# project_zasetskiy_DC-DC.net
KiCad netlist of a schematic drawn in Altium Designer
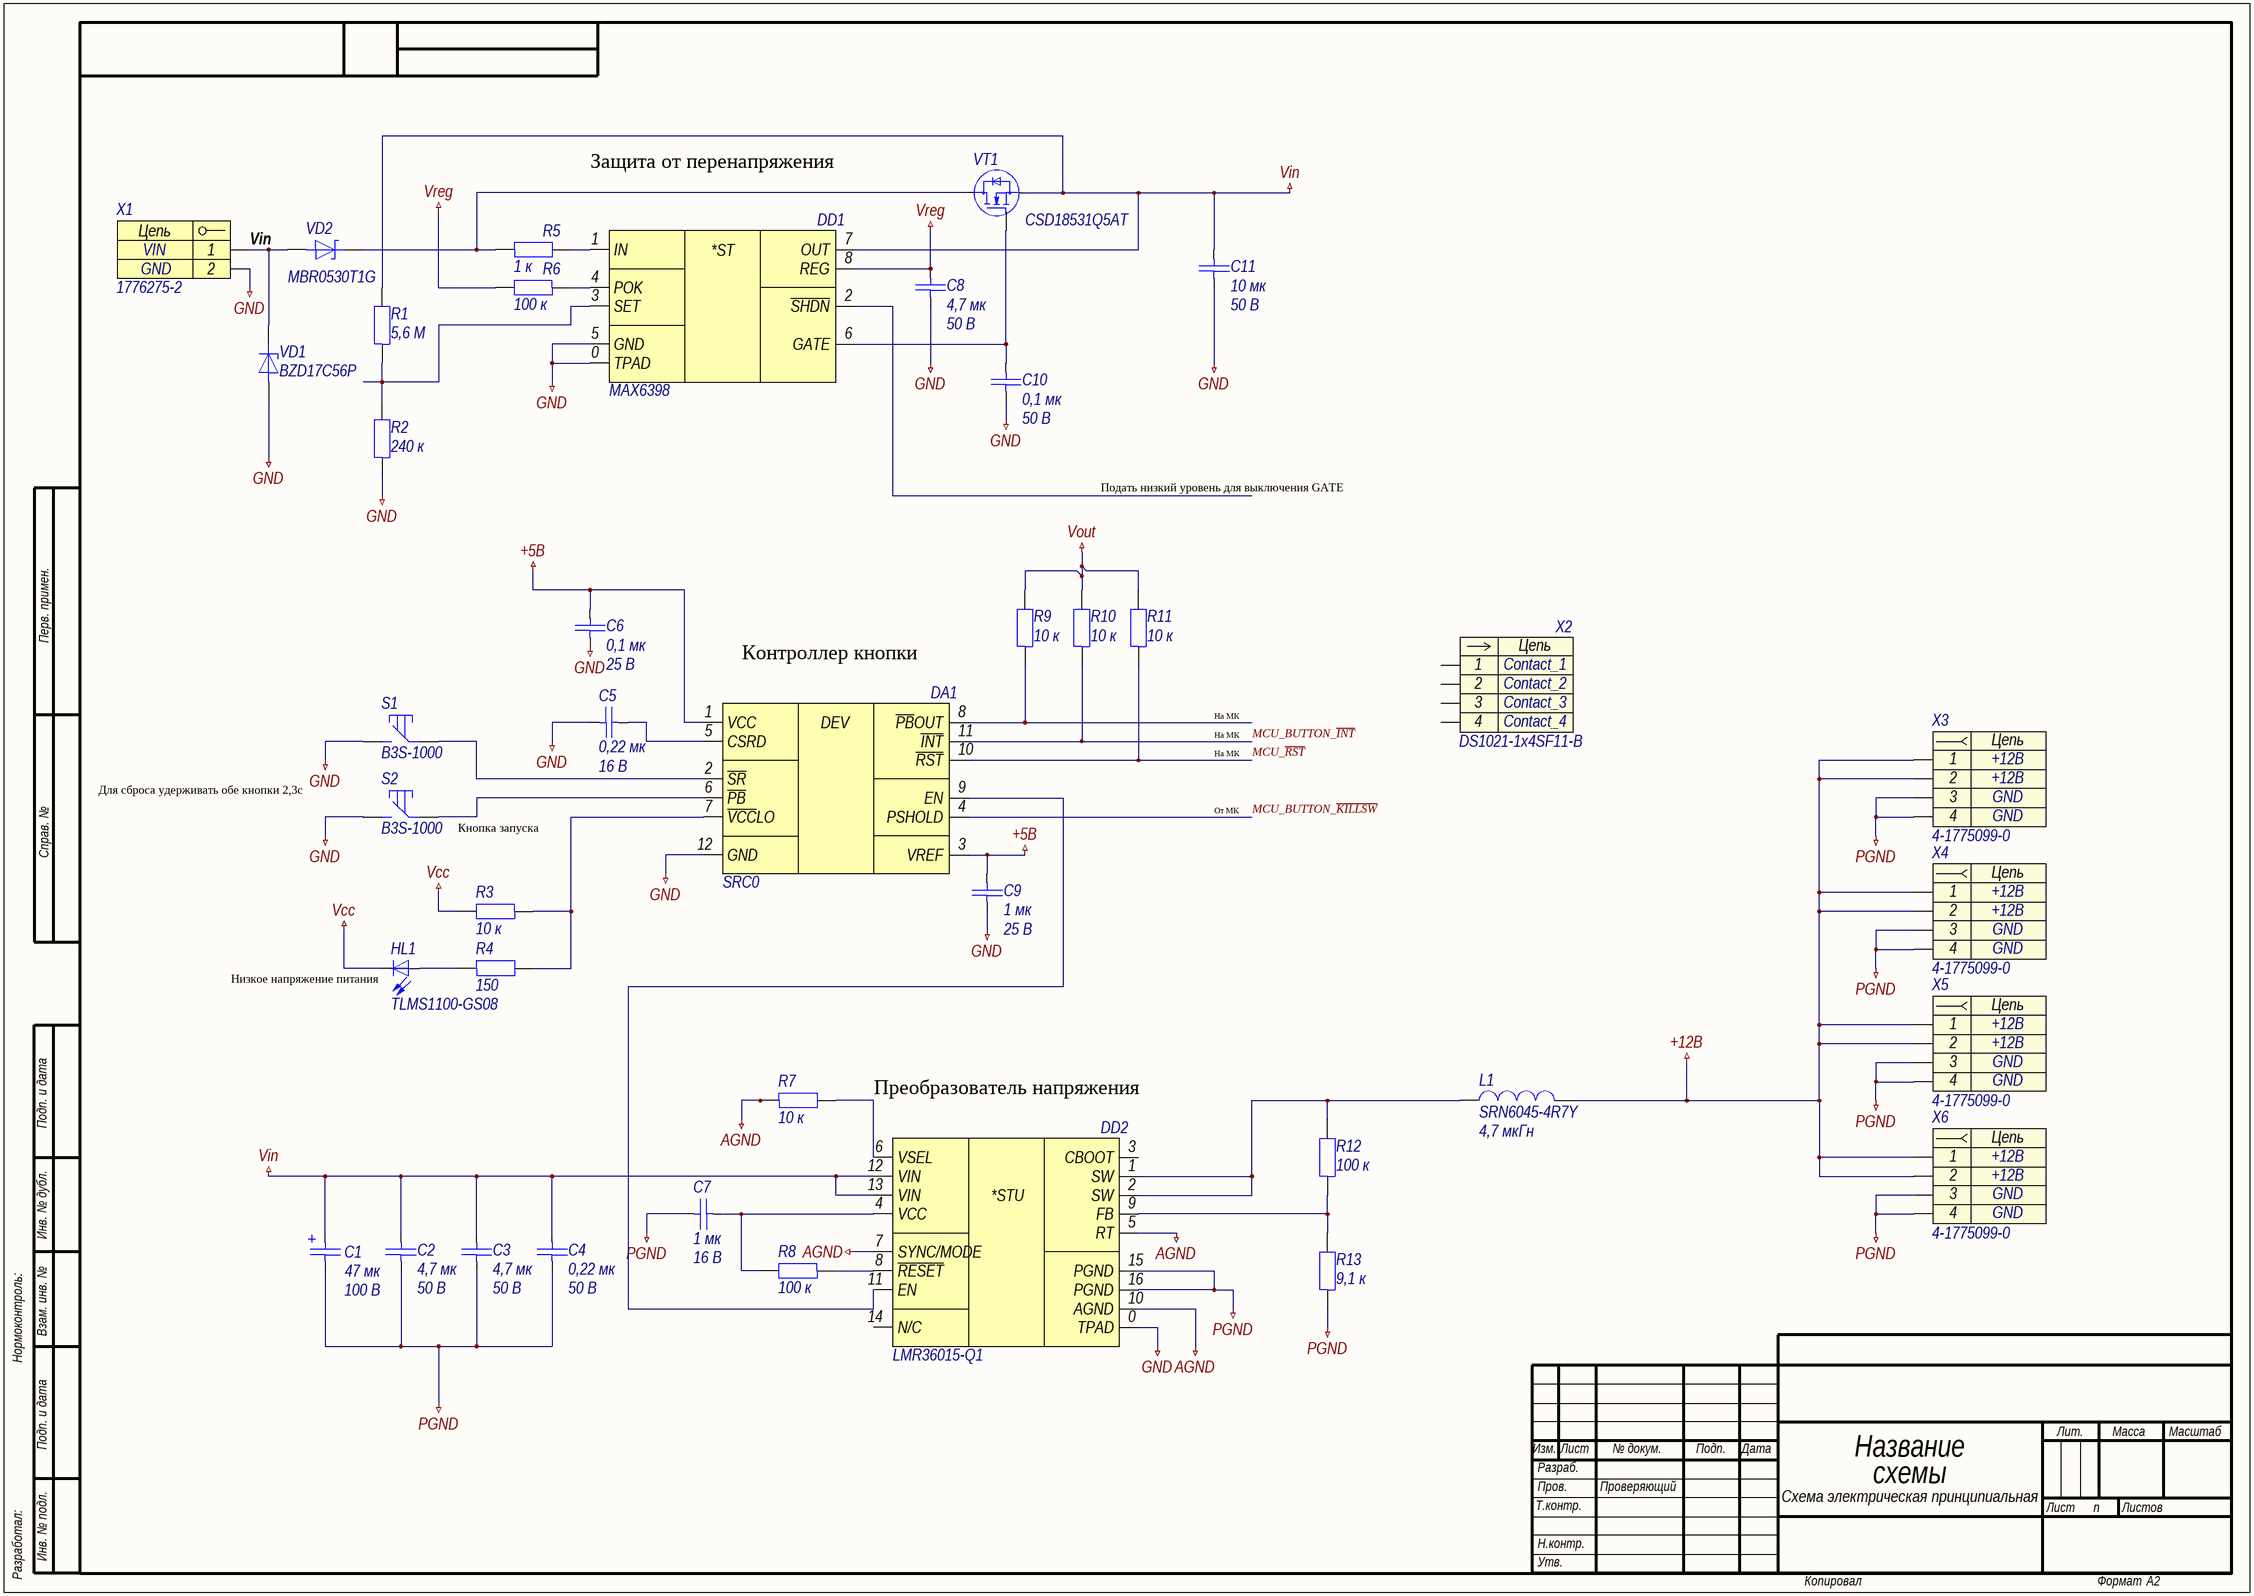
[diagram p0: project_zasetskiy_DC-DC.SchDoc]

(export (version "E")
  (design (tool "Eeschema 10.0.6"))
  (components
    (comp (ref "C1")
      (value "47 мк")
      (footprint "CAPAE-1000X1000X1200")
      (description "=Описание")
      (fields (field (name "НАПРЯЖЕНИЕ") "100 В"))
      (libsource (lib "Database_Students") (part "CAPACITOR-POLAR"))
    )
    (comp (ref "C2")
      (value "4,7 мк")
      (footprint "C1206")
      (description "=Описание")
      (fields (field (name "НАПРЯЖЕНИЕ") "50 В"))
      (libsource (lib "Database_Students") (part "CAPACITOR-NONPOLAR"))
    )
    (comp (ref "C3")
      (value "4,7 мк")
      (footprint "C1206")
      (description "=Описание")
      (fields (field (name "НАПРЯЖЕНИЕ") "50 В"))
      (libsource (lib "Database_Students") (part "CAPACITOR-NONPOLAR"))
    )
    (comp (ref "C4")
      (value "0,22 мк")
      (footprint "C0603")
      (description "=Описание")
      (fields (field (name "НАПРЯЖЕНИЕ") "50 В"))
      (libsource (lib "Database_Students") (part "CAPACITOR-NONPOLAR"))
    )
    (comp (ref "C5")
      (value "0,22 мк")
      (footprint "C0603")
      (description "=Описание")
      (fields (field (name "НАПРЯЖЕНИЕ") "16 В"))
      (libsource (lib "Database_Students") (part "CAPACITOR-NONPOLAR"))
    )
    (comp (ref "C6")
      (value "0,1 мк")
      (footprint "C0402")
      (description "=Описание")
      (fields (field (name "НАПРЯЖЕНИЕ") "25 В"))
      (libsource (lib "Database_Students") (part "CAPACITOR-NONPOLAR"))
    )
    (comp (ref "C7")
      (value "1 мк")
      (footprint "C0603")
      (description "=Описание")
      (fields (field (name "НАПРЯЖЕНИЕ") "16 В"))
      (libsource (lib "Database_Students") (part "CAPACITOR-NONPOLAR"))
    )
    (comp (ref "C8")
      (value "4,7 мк")
      (footprint "C1206")
      (description "=Описание")
      (fields (field (name "НАПРЯЖЕНИЕ") "50 В"))
      (libsource (lib "Database_Students") (part "CAPACITOR-NONPOLAR"))
    )
    (comp (ref "C9")
      (value "1 мк")
      (footprint "C0603")
      (description "=Описание")
      (fields (field (name "НАПРЯЖЕНИЕ") "25 В"))
      (libsource (lib "Database_Students") (part "CAPACITOR-NONPOLAR"))
    )
    (comp (ref "C10")
      (value "0,1 мк")
      (footprint "C0603")
      (description "=Описание")
      (fields (field (name "НАПРЯЖЕНИЕ") "50 В"))
      (libsource (lib "Database_Students") (part "CAPACITOR-NONPOLAR"))
    )
    (comp (ref "C11")
      (value "10 мк")
      (footprint "C1210")
      (description "=Описание")
      (fields (field (name "НАПРЯЖЕНИЕ") "50 В"))
      (libsource (lib "Database_Students") (part "CAPACITOR-NONPOLAR"))
    )
    (comp (ref "DA1")
      (value "SRC0")
      (description "=Описание")
      (libsource (lib "MyDatabase") (part "DA-SRC0"))
    )
    (comp (ref "DD1")
      (value "MAX6398")
      (description "=Описание")
      (libsource (lib "MyDatabase") (part "DD-MAX6398"))
    )
    (comp (ref "DD2")
      (value "LMR36015-Q1")
      (description "=Описание")
      (libsource (lib "MyDatabase") (part "DD-LM63635-Q1"))
    )
    (comp (ref "HL1")
      (value "TLMS1100-GS08")
      (footprint "LED")
      (description "=Описание")
      (libsource (lib "MyDatabase") (part "led"))
    )
    (comp (ref "L1")
      (value "SRN6045-4R7Y")
      (footprint "SRN-2-600X600X450")
      (description "=Описание")
      (fields (field (name "ИНДУКТИВНОСТЬ") "4,7 мкГн"))
      (libsource (lib "Database_Students") (part "INDUCTOR-COMMON"))
    )
    (comp (ref "R1")
      (value "5,6 M")
      (footprint "R0603")
      (description "=Описание")
      (libsource (lib "Database_Students") (part "RESISTOR-COMMON"))
    )
    (comp (ref "R2")
      (value "240 к")
      (footprint "R0603")
      (description "=Описание")
      (libsource (lib "Database_Students") (part "RESISTOR-COMMON"))
    )
    (comp (ref "R3")
      (value "10 к")
      (footprint "R0603")
      (description "=Описание")
      (libsource (lib "Database_Students") (part "RESISTOR-COMMON"))
    )
    (comp (ref "R4")
      (value "150")
      (footprint "R0603")
      (description "=Описание")
      (libsource (lib "Database_Students") (part "RESISTOR-COMMON"))
    )
    (comp (ref "R5")
      (value "1 к")
      (footprint "R0603")
      (description "=Описание")
      (libsource (lib "Database_Students") (part "RESISTOR-COMMON"))
    )
    (comp (ref "R6")
      (value "100 к")
      (footprint "R0603")
      (description "=Описание")
      (libsource (lib "Database_Students") (part "RESISTOR-COMMON"))
    )
    (comp (ref "R7")
      (value "10 к")
      (footprint "R0603")
      (description "=Описание")
      (libsource (lib "Database_Students") (part "RESISTOR-COMMON"))
    )
    (comp (ref "R8")
      (value "100 к")
      (footprint "R0603")
      (description "=Описание")
      (libsource (lib "Database_Students") (part "RESISTOR-COMMON"))
    )
    (comp (ref "R9")
      (value "10 к")
      (footprint "R0603")
      (description "=Описание")
      (libsource (lib "Database_Students") (part "RESISTOR-COMMON"))
    )
    (comp (ref "R10")
      (value "10 к")
      (footprint "R0603")
      (description "=Описание")
      (libsource (lib "Database_Students") (part "RESISTOR-COMMON"))
    )
    (comp (ref "R11")
      (value "10 к")
      (footprint "R0603")
      (description "=Описание")
      (libsource (lib "Database_Students") (part "RESISTOR-COMMON"))
    )
    (comp (ref "R12")
      (value "100 к")
      (footprint "R0603")
      (description "=Описание")
      (libsource (lib "Database_Students") (part "RESISTOR-COMMON"))
    )
    (comp (ref "R13")
      (value "9,1 к")
      (footprint "R0603")
      (description "=Описание")
      (libsource (lib "Database_Students") (part "RESISTOR-COMMON"))
    )
    (comp (ref "S1")
      (value "B3S-1000")
      (footprint "BUTTON")
      (description "=Описание")
      (libsource (lib "MyDatabase") (part "S-button"))
    )
    (comp (ref "S2")
      (value "B3S-1000")
      (footprint "BUTTON")
      (description "=Описание")
      (libsource (lib "MyDatabase") (part "S-button"))
    )
    (comp (ref "VD1")
      (value "BZD17C56P")
      (footprint "DO-219AB-280X180X108")
      (description "=Описание")
      (libsource (lib "Database_Students") (part "DIODE-ZENER"))
    )
    (comp (ref "VD2")
      (value "MBR0530T1G")
      (footprint "SOD-123-368X160X135")
      (description "=Описание")
      (libsource (lib "Database_Students") (part "DIODE-SCHOTTKY"))
    )
    (comp (ref "VT1")
      (value "CSD18531Q5AT")
      (footprint "VSONP-8-P127-600X500X110")
      (description "=Описание")
      (libsource (lib "Database_Students") (part "MOSFET-N-DIODE"))
    )
    (comp (ref "X1")
      (value "1776275-2")
      (footprint "1776275-2")
      (description "=Описание")
      (libsource (lib "Database_Students") (part "HEADER-2-TRM"))
    )
    (comp (ref "X2")
      (value "DS1021-1x4SF11-B")
      (footprint "DS1021-1X4SF11-B")
      (description "=Описание")
      (libsource (lib "Database_Students") (part "HEADER-4-PLG"))
    )
    (comp (ref "X3")
      (value "4-1775099-0")
      (footprint "4-1775099-0")
      (description "=Описание")
      (libsource (lib "Database_Students") (part "HEADER-4-SCT"))
    )
    (comp (ref "X4")
      (value "4-1775099-0")
      (footprint "4-1775099-0")
      (description "=Описание")
      (libsource (lib "Database_Students") (part "HEADER-4-SCT"))
    )
    (comp (ref "X5")
      (value "4-1775099-0")
      (footprint "4-1775099-0")
      (description "=Описание")
      (libsource (lib "Database_Students") (part "HEADER-4-SCT"))
    )
    (comp (ref "X6")
      (value "4-1775099-0")
      (footprint "4-1775099-0")
      (description "=Описание")
      (libsource (lib "Database_Students") (part "HEADER-4-SCT"))
    )
  )
  (nets
    (net (code "1") (name "+5В") (class "Default")
      (node (ref "C6") (pin "1") (pinfunction "1_1") (pintype "passive"))
      (node (ref "C9") (pin "1") (pinfunction "1_1") (pintype "passive"))
      (node (ref "DA1") (pin "1") (pinfunction "VCC_1") (pintype "passive"))
      (node (ref "DA1") (pin "3") (pinfunction "VREF_3") (pintype "passive"))
    )
    (net (code "2") (name "+12В") (class "Default")
      (node (ref "L1") (pin "2") (pinfunction "2_2") (pintype "passive"))
      (node (ref "X3") (pin "1") (pinfunction "1_1") (pintype "passive"))
      (node (ref "X3") (pin "2") (pinfunction "2_2") (pintype "passive"))
      (node (ref "X4") (pin "1") (pinfunction "1_1") (pintype "passive"))
      (node (ref "X4") (pin "2") (pinfunction "2_2") (pintype "passive"))
      (node (ref "X5") (pin "1") (pinfunction "1_1") (pintype "passive"))
      (node (ref "X5") (pin "2") (pinfunction "2_2") (pintype "passive"))
      (node (ref "X6") (pin "1") (pinfunction "1_1") (pintype "passive"))
      (node (ref "X6") (pin "2") (pinfunction "2_2") (pintype "passive"))
    )
    (net (code "3") (name "/MCU_BUTTON_~{INT}") (class "Default")
      (node (ref "DA1") (pin "11") (pinfunction "~{INT}_11") (pintype "passive"))
      (node (ref "R10") (pin "1") (pinfunction "1_1") (pintype "passive"))
    )
    (net (code "4") (name "/MCU_BUTTON_~{KILLSW}") (class "Default")
      (node (ref "DA1") (pin "4") (pinfunction "PSHOLD_4") (pintype "passive"))
    )
    (net (code "5") (name "/MCU_~{RST}") (class "Default")
      (node (ref "DA1") (pin "10") (pinfunction "~{RST}_10") (pintype "passive"))
      (node (ref "R11") (pin "1") (pinfunction "1_1") (pintype "passive"))
    )
    (net (code "6") (name "AGND") (class "Default")
      (node (ref "DD2") (pin "10") (pinfunction "AGND_10") (pintype "passive"))
      (node (ref "DD2") (pin "5") (pinfunction "RT_5") (pintype "passive"))
      (node (ref "DD2") (pin "7") (pinfunction "SYNC/MODE_7") (pintype "passive"))
      (node (ref "R7") (pin "1") (pinfunction "1_1") (pintype "passive"))
    )
    (net (code "7") (name "GND") (class "Default")
      (node (ref "C10") (pin "2") (pinfunction "2_2") (pintype "passive"))
      (node (ref "C11") (pin "2") (pinfunction "2_2") (pintype "passive"))
      (node (ref "C5") (pin "2") (pinfunction "2_2") (pintype "passive"))
      (node (ref "C6") (pin "2") (pinfunction "2_2") (pintype "passive"))
      (node (ref "C8") (pin "2") (pinfunction "2_2") (pintype "passive"))
      (node (ref "C9") (pin "2") (pinfunction "2_2") (pintype "passive"))
      (node (ref "DA1") (pin "12") (pinfunction "GND_12") (pintype "passive"))
      (node (ref "DD1") (pin "0") (pinfunction "TPAD_0") (pintype "passive"))
      (node (ref "DD1") (pin "5") (pinfunction "GND_5") (pintype "passive"))
      (node (ref "DD2") (pin "0") (pinfunction "TPAD_0") (pintype "passive"))
      (node (ref "R2") (pin "1") (pinfunction "1_1") (pintype "passive"))
      (node (ref "VD1") (pin "2") (pinfunction "2_2") (pintype "passive"))
      (node (ref "X1") (pin "2") (pinfunction "2_2") (pintype "passive"))
    )
    (net (code "8") (name "Net-(DA1-CSRD)") (class "Default")
      (node (ref "C5") (pin "1") (pinfunction "1_1") (pintype "passive"))
      (node (ref "DA1") (pin "5") (pinfunction "CSRD_5") (pintype "passive"))
    )
    (net (code "9") (name "Net-(DA1-EN)") (class "Default")
      (node (ref "DA1") (pin "9") (pinfunction "EN_9") (pintype "passive"))
      (node (ref "DD2") (pin "11") (pinfunction "EN_11") (pintype "passive"))
    )
    (net (code "10") (name "Net-(DA1-~{PB})") (class "Default")
      (node (ref "DA1") (pin "6") (pinfunction "~{PB}_6") (pintype "passive"))
      (node (ref "S2") (pin "2") (pinfunction "2_2") (pintype "passive"))
    )
    (net (code "11") (name "Net-(DA1-~{PB}OUT)") (class "Default")
      (node (ref "DA1") (pin "8") (pinfunction "~{PB}OUT_8") (pintype "passive"))
      (node (ref "R9") (pin "1") (pinfunction "1_1") (pintype "passive"))
    )
    (net (code "12") (name "Net-(DA1-~{SR})") (class "Default")
      (node (ref "DA1") (pin "2") (pinfunction "~{SR}_2") (pintype "passive"))
      (node (ref "S1") (pin "2") (pinfunction "2_2") (pintype "passive"))
    )
    (net (code "13") (name "Net-(DA1-~{VCC}LO)") (class "Default")
      (node (ref "DA1") (pin "7") (pinfunction "~{VCC}LO_7") (pintype "passive"))
      (node (ref "R3") (pin "1") (pinfunction "1_1") (pintype "passive"))
      (node (ref "R4") (pin "2") (pinfunction "2_2") (pintype "passive"))
    )
    (net (code "14") (name "Net-(DD1-GATE)") (class "Default")
      (node (ref "C10") (pin "1") (pinfunction "1_1") (pintype "passive"))
      (node (ref "DD1") (pin "6") (pinfunction "GATE_6") (pintype "passive"))
      (node (ref "VT1") (pin "G") (pinfunction "G_G") (pintype "passive"))
    )
    (net (code "15") (name "Net-(DD1-IN)") (class "Default")
      (node (ref "DD1") (pin "1") (pinfunction "IN_1") (pintype "passive"))
      (node (ref "R5") (pin "2") (pinfunction "2_2") (pintype "passive"))
    )
    (net (code "16") (name "Net-(DD1-POK)") (class "Default")
      (node (ref "DD1") (pin "4") (pinfunction "POK_4") (pintype "passive"))
      (node (ref "R6") (pin "1") (pinfunction "1_1") (pintype "passive"))
    )
    (net (code "17") (name "Net-(DD1-SET)") (class "Default")
      (node (ref "DD1") (pin "3") (pinfunction "SET_3") (pintype "passive"))
      (node (ref "R1") (pin "1") (pinfunction "1_1") (pintype "passive"))
      (node (ref "R2") (pin "2") (pinfunction "2_2") (pintype "passive"))
    )
    (net (code "18") (name "Net-(DD2-FB)") (class "Default")
      (node (ref "DD2") (pin "9") (pinfunction "FB_9") (pintype "passive"))
      (node (ref "R12") (pin "1") (pinfunction "1_1") (pintype "passive"))
      (node (ref "R13") (pin "2") (pinfunction "2_2") (pintype "passive"))
    )
    (net (code "19") (name "Net-(DD2-SW-Pad1)") (class "Default")
      (node (ref "DD2") (pin "1") (pinfunction "SW_1") (pintype "passive"))
      (node (ref "DD2") (pin "2") (pinfunction "SW_2") (pintype "passive"))
      (node (ref "L1") (pin "1") (pinfunction "1_1") (pintype "passive"))
      (node (ref "R12") (pin "2") (pinfunction "2_2") (pintype "passive"))
    )
    (net (code "20") (name "Net-(DD2-VCC)") (class "Default")
      (node (ref "C7") (pin "2") (pinfunction "2_2") (pintype "passive"))
      (node (ref "DD2") (pin "4") (pinfunction "VCC_4") (pintype "passive"))
      (node (ref "R8") (pin "2") (pinfunction "2_2") (pintype "passive"))
    )
    (net (code "21") (name "Net-(DD2-VSEL)") (class "Default")
      (node (ref "DD2") (pin "6") (pinfunction "VSEL_6") (pintype "passive"))
      (node (ref "R7") (pin "2") (pinfunction "2_2") (pintype "passive"))
    )
    (net (code "22") (name "Net-(DD2-~{RESET})") (class "Default")
      (node (ref "DD2") (pin "8") (pinfunction "~{RESET}_8") (pintype "passive"))
      (node (ref "R8") (pin "1") (pinfunction "1_1") (pintype "passive"))
    )
    (net (code "23") (name "Net-(HL1-A)") (class "Default")
      (node (ref "HL1") (pin "1") (pinfunction "A_1") (pintype "passive"))
      (node (ref "R4") (pin "1") (pinfunction "1_1") (pintype "passive"))
    )
    (net (code "24") (name "Net-(R5-Pad1)") (class "Default")
      (node (ref "R5") (pin "1") (pinfunction "1_1") (pintype "passive"))
      (node (ref "VD2") (pin "1") (pinfunction "1_1") (pintype "passive"))
      (node (ref "VT1") (pin "D") (pinfunction "D_D") (pintype "passive"))
    )
    (net (code "25") (name "Net-(VD1-Pad1)") (class "Default")
      (node (ref "VD1") (pin "1") (pinfunction "1_1") (pintype "passive"))
      (node (ref "VD2") (pin "2") (pinfunction "2_2") (pintype "passive"))
      (node (ref "X1") (pin "1") (pinfunction "1_1") (pintype "passive"))
    )
    (net (code "26") (name "PGND") (class "Default")
      (node (ref "C1") (pin "2") (pinfunction "2_2") (pintype "passive"))
      (node (ref "C2") (pin "2") (pinfunction "2_2") (pintype "passive"))
      (node (ref "C3") (pin "2") (pinfunction "2_2") (pintype "passive"))
      (node (ref "C4") (pin "2") (pinfunction "2_2") (pintype "passive"))
      (node (ref "C7") (pin "1") (pinfunction "1_1") (pintype "passive"))
      (node (ref "DD2") (pin "15") (pinfunction "PGND_15") (pintype "passive"))
      (node (ref "DD2") (pin "16") (pinfunction "PGND_16") (pintype "passive"))
      (node (ref "R13") (pin "1") (pinfunction "1_1") (pintype "passive"))
      (node (ref "X3") (pin "3") (pinfunction "3_3") (pintype "passive"))
      (node (ref "X3") (pin "4") (pinfunction "4_4") (pintype "passive"))
      (node (ref "X4") (pin "3") (pinfunction "3_3") (pintype "passive"))
      (node (ref "X4") (pin "4") (pinfunction "4_4") (pintype "passive"))
      (node (ref "X5") (pin "3") (pinfunction "3_3") (pintype "passive"))
      (node (ref "X5") (pin "4") (pinfunction "4_4") (pintype "passive"))
      (node (ref "X6") (pin "3") (pinfunction "3_3") (pintype "passive"))
      (node (ref "X6") (pin "4") (pinfunction "4_4") (pintype "passive"))
    )
    (net (code "27") (name "Vcc") (class "Default")
      (node (ref "HL1") (pin "2") (pinfunction "K_2") (pintype "passive"))
      (node (ref "R3") (pin "2") (pinfunction "2_2") (pintype "passive"))
    )
    (net (code "28") (name "Vin") (class "Default")
      (node (ref "C1") (pin "1") (pinfunction "1_1") (pintype "passive"))
      (node (ref "C11") (pin "1") (pinfunction "1_1") (pintype "passive"))
      (node (ref "C2") (pin "1") (pinfunction "1_1") (pintype "passive"))
      (node (ref "C3") (pin "1") (pinfunction "1_1") (pintype "passive"))
      (node (ref "C4") (pin "1") (pinfunction "1_1") (pintype "passive"))
      (node (ref "DD1") (pin "7") (pinfunction "OUT_7") (pintype "passive"))
      (node (ref "DD2") (pin "12") (pinfunction "VIN_12") (pintype "passive"))
      (node (ref "DD2") (pin "13") (pinfunction "VIN_13") (pintype "passive"))
      (node (ref "R1") (pin "2") (pinfunction "2_2") (pintype "passive"))
      (node (ref "VT1") (pin "S") (pinfunction "S_S") (pintype "passive"))
    )
    (net (code "29") (name "Vout") (class "Default")
      (node (ref "R10") (pin "2") (pinfunction "2_2") (pintype "passive"))
      (node (ref "R11") (pin "2") (pinfunction "2_2") (pintype "passive"))
      (node (ref "R9") (pin "2") (pinfunction "2_2") (pintype "passive"))
    )
    (net (code "30") (name "Vreg") (class "Default")
      (node (ref "C8") (pin "1") (pinfunction "1_1") (pintype "passive"))
      (node (ref "DD1") (pin "8") (pinfunction "REG_8") (pintype "passive"))
      (node (ref "R6") (pin "2") (pinfunction "2_2") (pintype "passive"))
    )
    (net (code "31") (name "unconnected-(DD1-~{SHDN}-Pad2)") (class "Default")
      (node (ref "DD1") (pin "2") (pinfunction "~{SHDN}_2") (pintype "passive"))
    )
    (net (code "32") (name "unconnected-(DD2-CBOOT-Pad3)") (class "Default")
      (node (ref "DD2") (pin "3") (pinfunction "CBOOT_3") (pintype "passive"))
    )
    (net (code "33") (name "unconnected-(DD2-N{slash}C-Pad14)") (class "Default")
      (node (ref "DD2") (pin "14") (pinfunction "N/C_14") (pintype "passive"))
    )
    (net (code "34") (name "unconnected-(S1-Pad1)") (class "Default")
      (node (ref "S1") (pin "1") (pinfunction "1_1") (pintype "passive"))
    )
    (net (code "35") (name "unconnected-(S2-Pad1)") (class "Default")
      (node (ref "S2") (pin "1") (pinfunction "1_1") (pintype "passive"))
    )
    (net (code "36") (name "unconnected-(X2-Pad1)") (class "Default")
      (node (ref "X2") (pin "1") (pinfunction "1_1") (pintype "passive"))
    )
    (net (code "37") (name "unconnected-(X2-Pad2)") (class "Default")
      (node (ref "X2") (pin "2") (pinfunction "2_2") (pintype "passive"))
    )
    (net (code "38") (name "unconnected-(X2-Pad3)") (class "Default")
      (node (ref "X2") (pin "3") (pinfunction "3_3") (pintype "passive"))
    )
    (net (code "39") (name "unconnected-(X2-Pad4)") (class "Default")
      (node (ref "X2") (pin "4") (pinfunction "4_4") (pintype "passive"))
    )
  )
)
